# Power_Conversion_sheet.net
KiCad netlist of a schematic drawn in Altium Designer
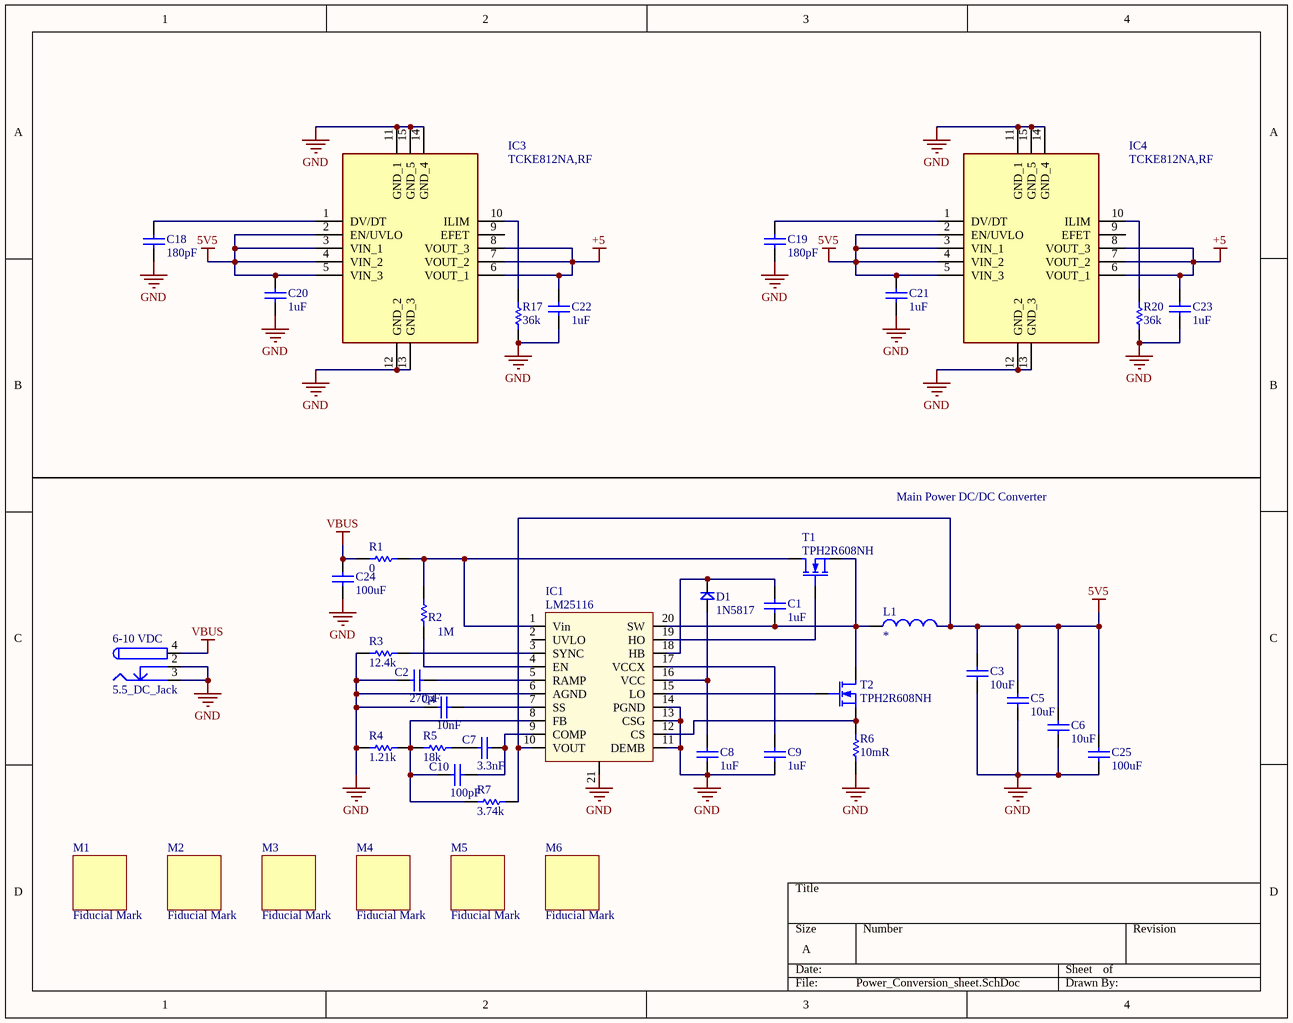
[diagram p0: Power_Conversion_sheet.SchDoc]

(export (version "E")
  (design (tool "Eeschema 10.0.6"))
  (components
    (comp (ref "6-10 VDC")
      (value "5.5_DC_Jack")
      (footprint "5.5_DC_Jack")
      (libsource (lib "Schlib_FPGA_Controller") (part "5.5_DC_Jack"))
    )
    (comp (ref "C1") (value "1uF") (footprint "C0603") (libsource (lib "Schlib1") (part "Cap")))
    (comp (ref "C2") (value "270pF") (footprint "C0603") (libsource (lib "Schlib1") (part "Cap")))
    (comp (ref "C3") (value "10uF") (footprint "C0603") (libsource (lib "Schlib1") (part "Cap")))
    (comp (ref "C4") (value "10nF") (footprint "C0603") (libsource (lib "Schlib1") (part "Cap")))
    (comp (ref "C5") (value "10uF") (footprint "C0603") (libsource (lib "Schlib1") (part "Cap")))
    (comp (ref "C6") (value "10uF") (footprint "C0603") (libsource (lib "Schlib1") (part "Cap")))
    (comp (ref "C7") (value "3.3nF") (footprint "C0603") (libsource (lib "Schlib1") (part "Cap")))
    (comp (ref "C8") (value "1uF") (footprint "C0603") (libsource (lib "Schlib1") (part "Cap")))
    (comp (ref "C9") (value "1uF") (footprint "C0603") (libsource (lib "Schlib1") (part "Cap")))
    (comp (ref "C10") (value "100pF") (footprint "C0603") (libsource (lib "Schlib1") (part "Cap")))
    (comp (ref "C18")
      (value "180pF")
      (footprint "C0603")
      (libsource (lib "Schlib_FPGA_Controller") (part "Cap"))
    )
    (comp (ref "C19")
      (value "180pF")
      (footprint "C0603")
      (libsource (lib "Schlib_FPGA_Controller") (part "Cap"))
    )
    (comp (ref "C20")
      (value "1uF")
      (footprint "C0603")
      (libsource (lib "Schlib_FPGA_Controller") (part "Cap"))
    )
    (comp (ref "C21")
      (value "1uF")
      (footprint "C0603")
      (libsource (lib "Schlib_FPGA_Controller") (part "Cap"))
    )
    (comp (ref "C22")
      (value "1uF")
      (footprint "C0603")
      (libsource (lib "Schlib_FPGA_Controller") (part "Cap"))
    )
    (comp (ref "C23")
      (value "1uF")
      (footprint "C0603")
      (libsource (lib "Schlib_FPGA_Controller") (part "Cap"))
    )
    (comp (ref "C24")
      (value "100uF")
      (footprint "C1206")
      (libsource (lib "Schlib_FPGA_Controller") (part "Cap"))
    )
    (comp (ref "C25")
      (value "100uF")
      (footprint "C1206")
      (libsource (lib "Schlib_FPGA_Controller") (part "Cap"))
    )
    (comp (ref "D1") (value "1N5817") (footprint "Diode-SOD-323") (libsource (lib "Schlib1") (part "Diode")))
    (comp (ref "IC1")
      (value "LM25116")
      (footprint "HTSSOP-20")
      (description "Buck Controller")
      (libsource (lib "Schlib1") (part "LM25116"))
    )
    (comp (ref "IC3")
      (value "TCKE812NA,RF")
      (footprint "SamacSys:TCKE812NARF")
      (description "Integrated Circuit")
      (fields (field (name "MOUSER PART NUMBER") "757-TCKE812NA,RF"))
      (libsource (lib "*") (part "TCKE812NA,RF"))
    )
    (comp (ref "IC4")
      (value "TCKE812NA,RF")
      (footprint "SamacSys:TCKE812NARF")
      (description "Integrated Circuit")
      (fields (field (name "MOUSER PART NUMBER") "757-TCKE812NA,RF"))
      (libsource (lib "*") (part "TCKE812NA,RF"))
    )
    (comp (ref "L1") (value "*") (footprint "Inductor-CDEP147") (libsource (lib "Schlib1") (part "Inductor")))
    (comp (ref "M1")
      (value "Fiducial Mark")
      (footprint "fiducial mark")
      (libsource (lib "Schlib_FPGA_Controller") (part "Fiducial Mark"))
    )
    (comp (ref "M2")
      (value "Fiducial Mark")
      (footprint "fiducial mark")
      (libsource (lib "Schlib_FPGA_Controller") (part "Fiducial Mark"))
    )
    (comp (ref "M3")
      (value "Fiducial Mark")
      (footprint "fiducial mark")
      (libsource (lib "Schlib_FPGA_Controller") (part "Fiducial Mark"))
    )
    (comp (ref "M4")
      (value "Fiducial Mark")
      (footprint "fiducial mark")
      (libsource (lib "Schlib_FPGA_Controller") (part "Fiducial Mark"))
    )
    (comp (ref "M5")
      (value "Fiducial Mark")
      (footprint "fiducial mark")
      (libsource (lib "Schlib_FPGA_Controller") (part "Fiducial Mark"))
    )
    (comp (ref "M6")
      (value "Fiducial Mark")
      (footprint "fiducial mark")
      (libsource (lib "Schlib_FPGA_Controller") (part "Fiducial Mark"))
    )
    (comp (ref "R1") (value "0") (footprint "R2010") (libsource (lib "Schlib1") (part "Resistor")))
    (comp (ref "R2") (value "1M") (footprint "R0603") (libsource (lib "Schlib1") (part "Resistor")))
    (comp (ref "R3") (value "12.4k") (footprint "R0603") (libsource (lib "Schlib1") (part "Resistor")))
    (comp (ref "R4") (value "1.21k") (footprint "R0603") (libsource (lib "Schlib1") (part "Resistor")))
    (comp (ref "R5") (value "18k") (footprint "R0603") (libsource (lib "Schlib1") (part "Resistor")))
    (comp (ref "R6") (value "10mR") (footprint "R2010") (libsource (lib "Schlib1") (part "Resistor")))
    (comp (ref "R7") (value "3.74k") (footprint "R0603") (libsource (lib "Schlib1") (part "Resistor")))
    (comp (ref "R17")
      (value "36k")
      (footprint "R0603")
      (description "The current limit is in 3A.")
      (libsource (lib "Schlib_FPGA_Controller") (part "Resistor"))
    )
    (comp (ref "R20")
      (value "36k")
      (footprint "R0603")
      (description "The current limit is in 3A.")
      (libsource (lib "Schlib_FPGA_Controller") (part "Resistor"))
    )
    (comp (ref "T1")
      (value "TPH2R608NH")
      (footprint "TPH2R608NH")
      (libsource (lib "Schlib1") (part "MOSFET-N"))
    )
    (comp (ref "T2")
      (value "TPH2R608NH")
      (footprint "TPH2R608NH")
      (libsource (lib "Schlib1") (part "MOSFET-N"))
    )
  )
  (nets
    (net (code "1") (name "+5") (class "Default")
      (node (ref "C22") (pin "2") (pinfunction "2_2") (pintype "passive"))
      (node (ref "C23") (pin "2") (pinfunction "2_2") (pintype "passive"))
      (node (ref "IC3") (pin "6") (pinfunction "VOUT_1_6") (pintype "passive"))
      (node (ref "IC3") (pin "7") (pinfunction "VOUT_2_7") (pintype "passive"))
      (node (ref "IC3") (pin "8") (pinfunction "VOUT_3_8") (pintype "passive"))
      (node (ref "IC4") (pin "6") (pinfunction "VOUT_1_6") (pintype "passive"))
      (node (ref "IC4") (pin "7") (pinfunction "VOUT_2_7") (pintype "passive"))
      (node (ref "IC4") (pin "8") (pinfunction "VOUT_3_8") (pintype "passive"))
    )
    (net (code "2") (name "5V5") (class "Default")
      (node (ref "C20") (pin "2") (pinfunction "2_2") (pintype "passive"))
      (node (ref "C21") (pin "2") (pinfunction "2_2") (pintype "passive"))
      (node (ref "C25") (pin "2") (pinfunction "2_2") (pintype "passive"))
      (node (ref "C3") (pin "2") (pinfunction "2_2") (pintype "passive"))
      (node (ref "C5") (pin "2") (pinfunction "2_2") (pintype "passive"))
      (node (ref "C6") (pin "2") (pinfunction "2_2") (pintype "passive"))
      (node (ref "IC1") (pin "10") (pinfunction "VOUT_10") (pintype "passive"))
      (node (ref "IC3") (pin "2") (pinfunction "EN/UVLO_2") (pintype "passive"))
      (node (ref "IC3") (pin "3") (pinfunction "VIN_1_3") (pintype "passive"))
      (node (ref "IC3") (pin "4") (pinfunction "VIN_2_4") (pintype "passive"))
      (node (ref "IC3") (pin "5") (pinfunction "VIN_3_5") (pintype "passive"))
      (node (ref "IC4") (pin "2") (pinfunction "EN/UVLO_2") (pintype "passive"))
      (node (ref "IC4") (pin "3") (pinfunction "VIN_1_3") (pintype "passive"))
      (node (ref "IC4") (pin "4") (pinfunction "VIN_2_4") (pintype "passive"))
      (node (ref "IC4") (pin "5") (pinfunction "VIN_3_5") (pintype "passive"))
      (node (ref "L1") (pin "2") (pinfunction "2_2") (pintype "passive"))
      (node (ref "R7") (pin "2") (pinfunction "2_2") (pintype "passive"))
    )
    (net (code "3") (name "GND") (class "Default")
      (node (ref "6-10 VDC") (pin "2") (pinfunction "2_2") (pintype "power_in"))
      (node (ref "6-10 VDC") (pin "3") (pinfunction "3_3") (pintype "power_in"))
      (node (ref "C18") (pin "1") (pinfunction "1_1") (pintype "passive"))
      (node (ref "C19") (pin "1") (pinfunction "1_1") (pintype "passive"))
      (node (ref "C2") (pin "1") (pinfunction "1_1") (pintype "passive"))
      (node (ref "C20") (pin "1") (pinfunction "1_1") (pintype "passive"))
      (node (ref "C21") (pin "1") (pinfunction "1_1") (pintype "passive"))
      (node (ref "C22") (pin "1") (pinfunction "1_1") (pintype "passive"))
      (node (ref "C23") (pin "1") (pinfunction "1_1") (pintype "passive"))
      (node (ref "C24") (pin "1") (pinfunction "1_1") (pintype "passive"))
      (node (ref "C25") (pin "1") (pinfunction "1_1") (pintype "passive"))
      (node (ref "C3") (pin "1") (pinfunction "1_1") (pintype "passive"))
      (node (ref "C4") (pin "1") (pinfunction "1_1") (pintype "passive"))
      (node (ref "C5") (pin "1") (pinfunction "1_1") (pintype "passive"))
      (node (ref "C6") (pin "1") (pinfunction "1_1") (pintype "passive"))
      (node (ref "C8") (pin "1") (pinfunction "1_1") (pintype "passive"))
      (node (ref "C9") (pin "1") (pinfunction "1_1") (pintype "passive"))
      (node (ref "IC1") (pin "11") (pinfunction "DEMB_11") (pintype "passive"))
      (node (ref "IC1") (pin "13") (pinfunction "CSG_13") (pintype "passive"))
      (node (ref "IC1") (pin "14") (pinfunction "PGND_14") (pintype "passive"))
      (node (ref "IC1") (pin "21") (pinfunction "21_21") (pintype "passive"))
      (node (ref "IC1") (pin "6") (pinfunction "AGND_6") (pintype "passive"))
      (node (ref "IC3") (pin "11") (pinfunction "GND_1_11") (pintype "passive"))
      (node (ref "IC3") (pin "12") (pinfunction "GND_2_12") (pintype "passive"))
      (node (ref "IC3") (pin "13") (pinfunction "GND_3_13") (pintype "passive"))
      (node (ref "IC3") (pin "14") (pinfunction "GND_4_14") (pintype "passive"))
      (node (ref "IC3") (pin "15") (pinfunction "GND_5_15") (pintype "passive"))
      (node (ref "IC4") (pin "11") (pinfunction "GND_1_11") (pintype "passive"))
      (node (ref "IC4") (pin "12") (pinfunction "GND_2_12") (pintype "passive"))
      (node (ref "IC4") (pin "13") (pinfunction "GND_3_13") (pintype "passive"))
      (node (ref "IC4") (pin "14") (pinfunction "GND_4_14") (pintype "passive"))
      (node (ref "IC4") (pin "15") (pinfunction "GND_5_15") (pintype "passive"))
      (node (ref "R17") (pin "1") (pinfunction "1_1") (pintype "passive"))
      (node (ref "R20") (pin "1") (pinfunction "1_1") (pintype "passive"))
      (node (ref "R3") (pin "1") (pinfunction "1_1") (pintype "passive"))
      (node (ref "R4") (pin "1") (pinfunction "1_1") (pintype "passive"))
      (node (ref "R6") (pin "1") (pinfunction "1_1") (pintype "passive"))
    )
    (net (code "4") (name "Net-(C7-Pad1)") (class "Default")
      (node (ref "C7") (pin "1") (pinfunction "1_1") (pintype "passive"))
      (node (ref "R5") (pin "1") (pinfunction "1_1") (pintype "passive"))
    )
    (net (code "5") (name "Net-(D1-ANODE)") (class "Default")
      (node (ref "C8") (pin "2") (pinfunction "2_2") (pintype "passive"))
      (node (ref "D1") (pin "1") (pinfunction "ANODE_1") (pintype "passive"))
      (node (ref "IC1") (pin "16") (pinfunction "VCC_16") (pintype "passive"))
    )
    (net (code "6") (name "Net-(D1-KATHODE)") (class "Default")
      (node (ref "C1") (pin "2") (pinfunction "2_2") (pintype "passive"))
      (node (ref "D1") (pin "2") (pinfunction "KATHODE_2") (pintype "passive"))
      (node (ref "IC1") (pin "18") (pinfunction "HB_18") (pintype "passive"))
    )
    (net (code "7") (name "Net-(IC1-COMP)") (class "Default")
      (node (ref "C10") (pin "2") (pinfunction "2_2") (pintype "passive"))
      (node (ref "C7") (pin "2") (pinfunction "2_2") (pintype "passive"))
      (node (ref "IC1") (pin "9") (pinfunction "COMP_9") (pintype "passive"))
    )
    (net (code "8") (name "Net-(IC1-CS)") (class "Default")
      (node (ref "IC1") (pin "12") (pinfunction "CS_12") (pintype "passive"))
      (node (ref "R6") (pin "2") (pinfunction "2_2") (pintype "passive"))
      (node (ref "T2") (pin "3") (pinfunction "S_3") (pintype "passive"))
    )
    (net (code "9") (name "Net-(IC1-EN)") (class "Default")
      (node (ref "IC1") (pin "4") (pinfunction "EN_4") (pintype "passive"))
      (node (ref "R2") (pin "2") (pinfunction "2_2") (pintype "passive"))
    )
    (net (code "10") (name "Net-(IC1-FB)") (class "Default")
      (node (ref "C10") (pin "1") (pinfunction "1_1") (pintype "passive"))
      (node (ref "IC1") (pin "8") (pinfunction "FB_8") (pintype "passive"))
      (node (ref "R4") (pin "2") (pinfunction "2_2") (pintype "passive"))
      (node (ref "R5") (pin "2") (pinfunction "2_2") (pintype "passive"))
      (node (ref "R7") (pin "1") (pinfunction "1_1") (pintype "passive"))
    )
    (net (code "11") (name "Net-(IC1-HO)") (class "Default")
      (node (ref "IC1") (pin "19") (pinfunction "HO_19") (pintype "passive"))
      (node (ref "T1") (pin "2") (pinfunction "G_2") (pintype "passive"))
    )
    (net (code "12") (name "Net-(IC1-LO)") (class "Default")
      (node (ref "IC1") (pin "15") (pinfunction "LO_15") (pintype "passive"))
      (node (ref "T2") (pin "2") (pinfunction "G_2") (pintype "passive"))
    )
    (net (code "13") (name "Net-(IC1-RAMP)") (class "Default")
      (node (ref "C2") (pin "2") (pinfunction "2_2") (pintype "passive"))
      (node (ref "IC1") (pin "5") (pinfunction "RAMP_5") (pintype "passive"))
    )
    (net (code "14") (name "Net-(IC1-SS)") (class "Default")
      (node (ref "C4") (pin "2") (pinfunction "2_2") (pintype "passive"))
      (node (ref "IC1") (pin "7") (pinfunction "SS_7") (pintype "passive"))
    )
    (net (code "15") (name "Net-(IC1-SW)") (class "Default")
      (node (ref "C1") (pin "1") (pinfunction "1_1") (pintype "passive"))
      (node (ref "IC1") (pin "20") (pinfunction "SW_20") (pintype "passive"))
      (node (ref "L1") (pin "1") (pinfunction "1_1") (pintype "passive"))
      (node (ref "T1") (pin "3") (pinfunction "S_3") (pintype "passive"))
      (node (ref "T2") (pin "1") (pinfunction "D_1") (pintype "passive"))
    )
    (net (code "16") (name "Net-(IC1-SYNC)") (class "Default")
      (node (ref "IC1") (pin "3") (pinfunction "SYNC_3") (pintype "passive"))
      (node (ref "R3") (pin "2") (pinfunction "2_2") (pintype "passive"))
    )
    (net (code "17") (name "Net-(IC1-VCCX)") (class "Default")
      (node (ref "C9") (pin "2") (pinfunction "2_2") (pintype "passive"))
      (node (ref "IC1") (pin "17") (pinfunction "VCCX_17") (pintype "passive"))
    )
    (net (code "18") (name "Net-(IC1-Vin)") (class "Default")
      (node (ref "IC1") (pin "1") (pinfunction "Vin_1") (pintype "passive"))
      (node (ref "R1") (pin "2") (pinfunction "2_2") (pintype "passive"))
      (node (ref "R2") (pin "1") (pinfunction "1_1") (pintype "passive"))
      (node (ref "T1") (pin "1") (pinfunction "D_1") (pintype "passive"))
    )
    (net (code "19") (name "Net-(IC3-DV{slash}DT)") (class "Default")
      (node (ref "C18") (pin "2") (pinfunction "2_2") (pintype "passive"))
      (node (ref "IC3") (pin "1") (pinfunction "DV/DT_1") (pintype "passive"))
    )
    (net (code "20") (name "Net-(IC3-ILIM)") (class "Default")
      (node (ref "IC3") (pin "10") (pinfunction "ILIM_10") (pintype "passive"))
      (node (ref "R17") (pin "2") (pinfunction "2_2") (pintype "passive"))
    )
    (net (code "21") (name "Net-(IC4-DV{slash}DT)") (class "Default")
      (node (ref "C19") (pin "2") (pinfunction "2_2") (pintype "passive"))
      (node (ref "IC4") (pin "1") (pinfunction "DV/DT_1") (pintype "passive"))
    )
    (net (code "22") (name "Net-(IC4-ILIM)") (class "Default")
      (node (ref "IC4") (pin "10") (pinfunction "ILIM_10") (pintype "passive"))
      (node (ref "R20") (pin "2") (pinfunction "2_2") (pintype "passive"))
    )
    (net (code "23") (name "VBUS") (class "Default")
      (node (ref "6-10 VDC") (pin "4") (pinfunction "4_4") (pintype "passive"))
      (node (ref "C24") (pin "2") (pinfunction "2_2") (pintype "passive"))
      (node (ref "R1") (pin "1") (pinfunction "1_1") (pintype "passive"))
    )
    (net (code "24") (name "unconnected-(IC1-UVLO-Pad2)") (class "Default")
      (node (ref "IC1") (pin "2") (pinfunction "UVLO_2") (pintype "passive"))
    )
    (net (code "25") (name "unconnected-(IC3-EFET-Pad9)") (class "Default")
      (node (ref "IC3") (pin "9") (pinfunction "EFET_9") (pintype "passive"))
    )
    (net (code "26") (name "unconnected-(IC4-EFET-Pad9)") (class "Default")
      (node (ref "IC4") (pin "9") (pinfunction "EFET_9") (pintype "passive"))
    )
  )
)
